# Hub_USB_2_0.net
KiCad netlist of a schematic drawn in EAGLE
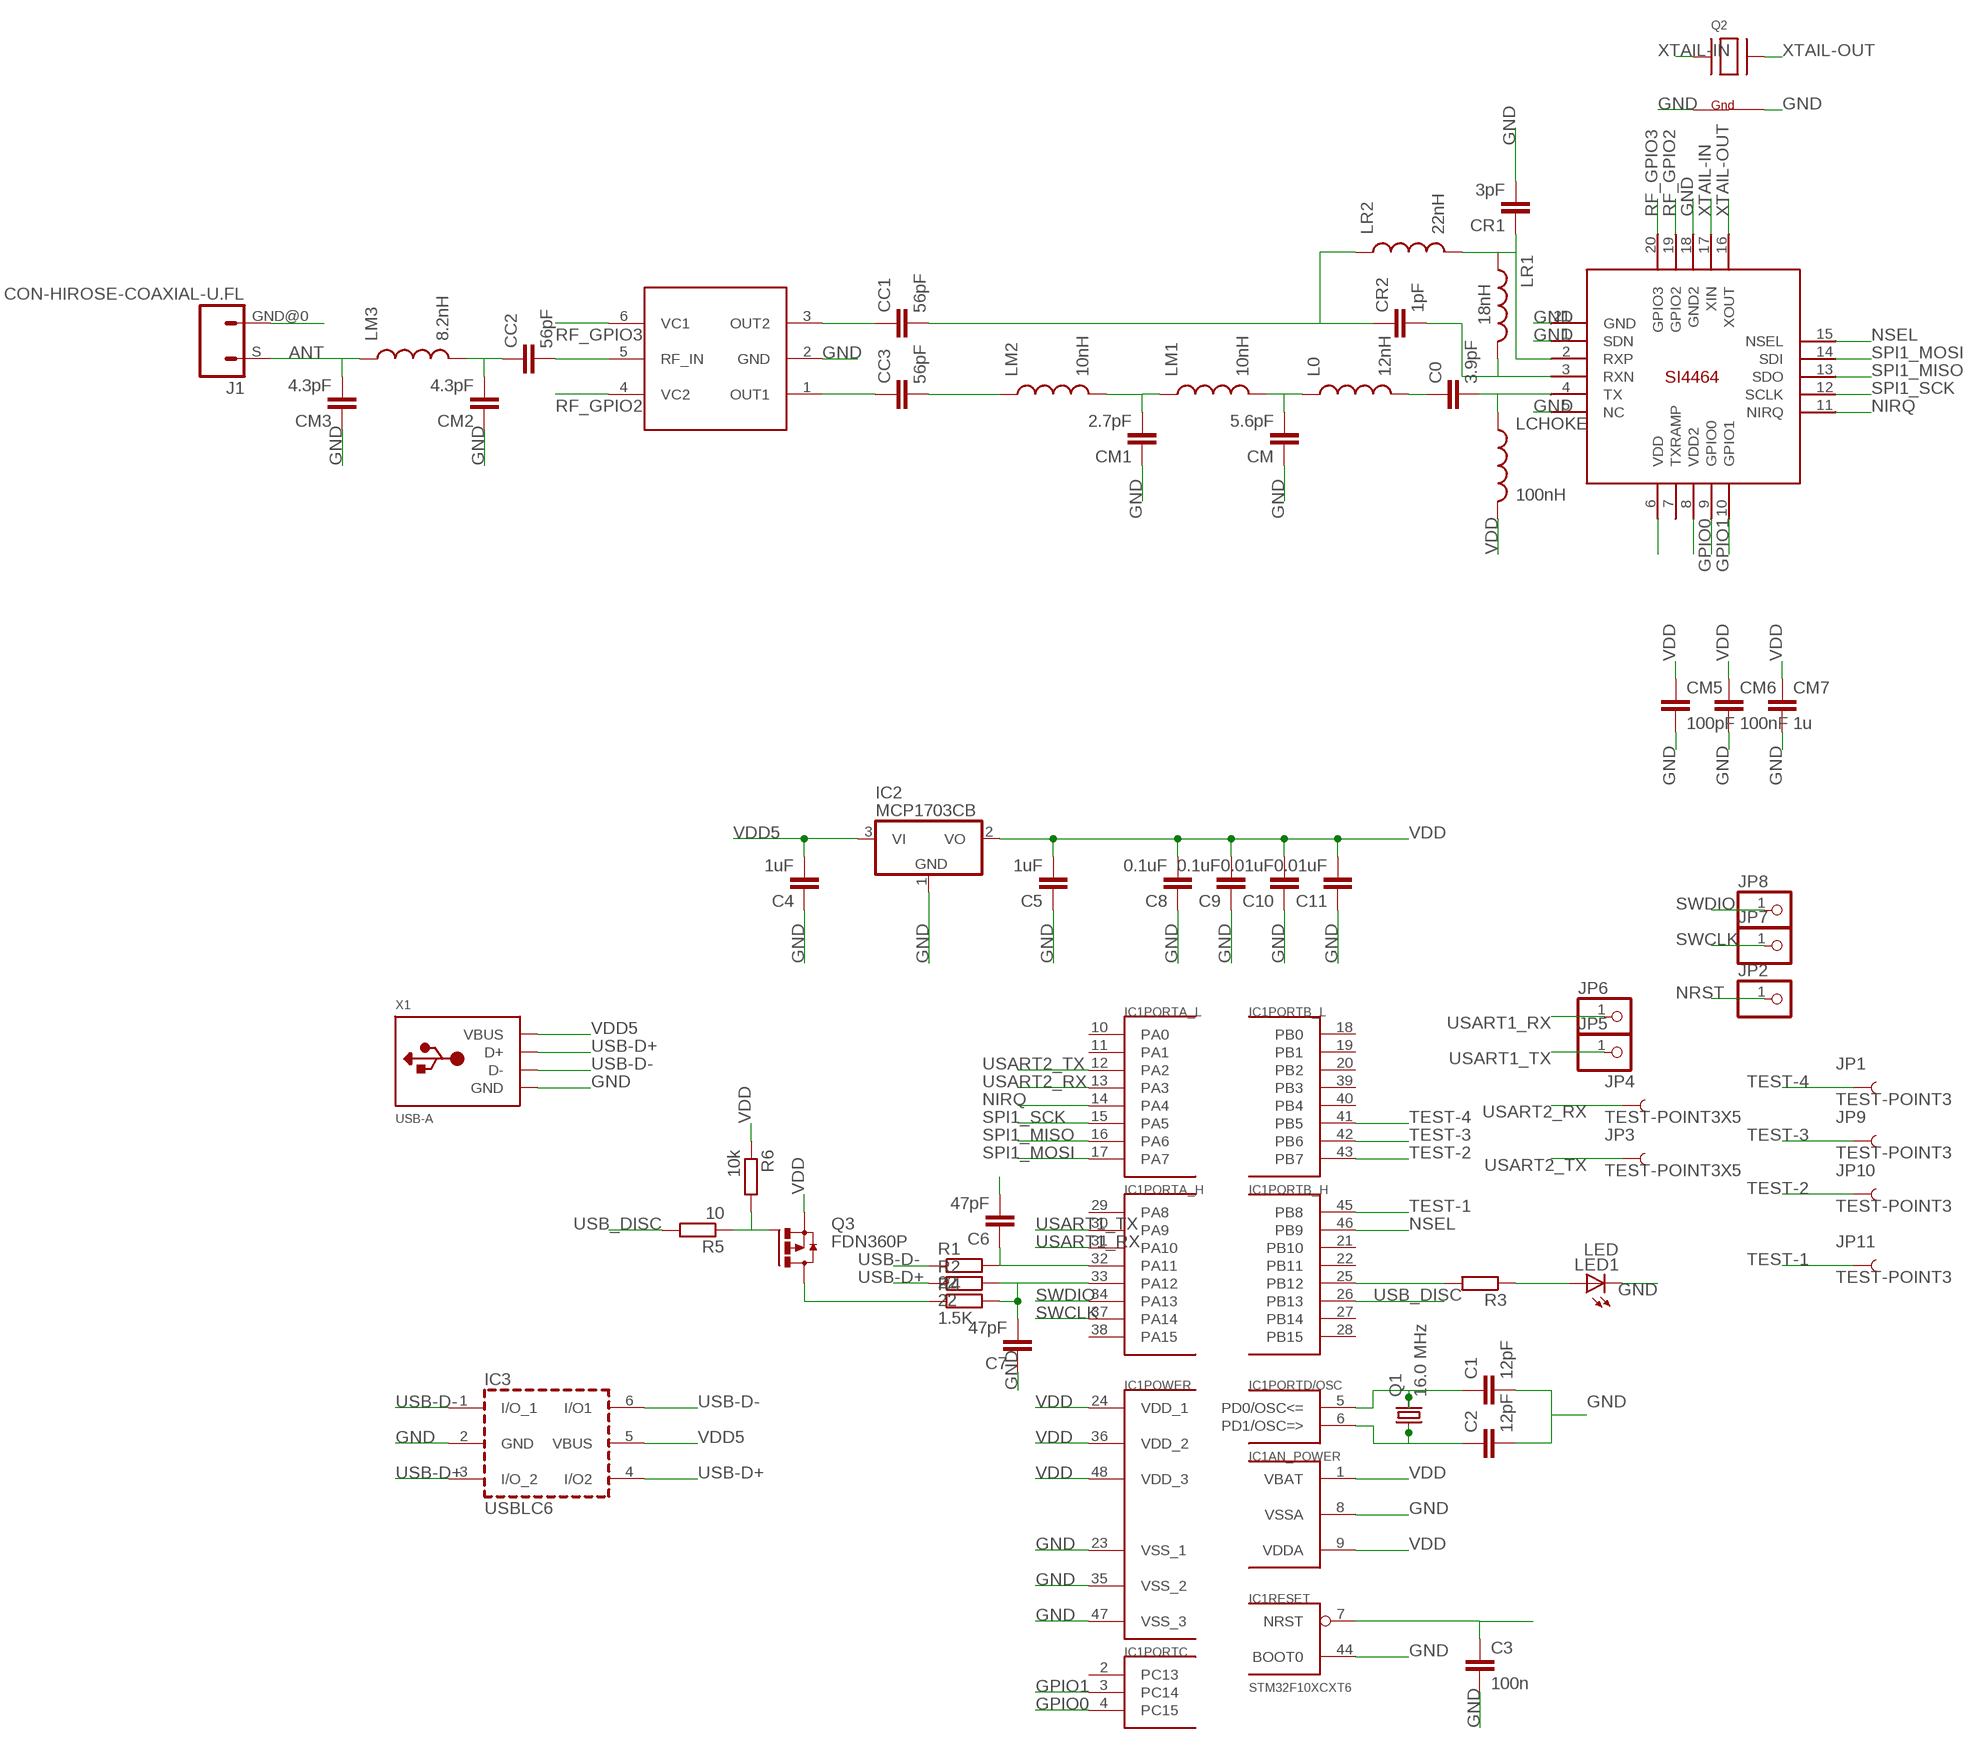
[diagram p0: schematic, sheet 1]

(export (version "E")
  (design (tool "Eeschema 10.0.6"))
  (components
    (comp (ref "C0")
      (value "3.9pF")
      (footprint "eagle-import:C0402")
      (libsource (lib "eagle-import") (part "C-EUC0402"))
    )
    (comp (ref "C1")
      (value "12pF")
      (footprint "eagle-import:C0603K")
      (libsource (lib "eagle-import") (part "C-EUC0603K"))
    )
    (comp (ref "C2")
      (value "12pF")
      (footprint "eagle-import:C0603K")
      (libsource (lib "eagle-import") (part "C-EUC0603K"))
    )
    (comp (ref "C3")
      (value "100n")
      (footprint "eagle-import:C0805")
      (libsource (lib "eagle-import") (part "C-EUC0805"))
    )
    (comp (ref "C4")
      (value "1uF")
      (footprint "eagle-import:C0805")
      (libsource (lib "eagle-import") (part "C-EUC0805"))
    )
    (comp (ref "C5")
      (value "1uF")
      (footprint "eagle-import:C0805")
      (libsource (lib "eagle-import") (part "C-EUC0805"))
    )
    (comp (ref "C6")
      (value "47pF")
      (footprint "eagle-import:C0805")
      (libsource (lib "eagle-import") (part "C-EUC0805"))
    )
    (comp (ref "C7")
      (value "47pF")
      (footprint "eagle-import:C0805")
      (libsource (lib "eagle-import") (part "C-EUC0805"))
    )
    (comp (ref "C8")
      (value "0.1uF")
      (footprint "eagle-import:C0805")
      (libsource (lib "eagle-import") (part "C-EUC0805"))
    )
    (comp (ref "C9")
      (value "0.1uF")
      (footprint "eagle-import:C0805")
      (libsource (lib "eagle-import") (part "C-EUC0805"))
    )
    (comp (ref "C10")
      (value "0.01uF")
      (footprint "eagle-import:C0805")
      (libsource (lib "eagle-import") (part "C-EUC0805"))
    )
    (comp (ref "C11")
      (value "0.01uF")
      (footprint "eagle-import:C0805")
      (libsource (lib "eagle-import") (part "C-EUC0805"))
    )
    (comp (ref "CC1")
      (value "56pF")
      (footprint "eagle-import:C0402")
      (libsource (lib "eagle-import") (part "C-EUC0402"))
    )
    (comp (ref "CC2")
      (value "56pF")
      (footprint "eagle-import:C0402")
      (libsource (lib "eagle-import") (part "C-EUC0402"))
    )
    (comp (ref "CC3")
      (value "56pF")
      (footprint "eagle-import:C0402")
      (libsource (lib "eagle-import") (part "C-EUC0402"))
    )
    (comp (ref "CM")
      (value "5.6pF")
      (footprint "eagle-import:C0402")
      (libsource (lib "eagle-import") (part "C-EUC0402"))
    )
    (comp (ref "CM1")
      (value "2.7pF")
      (footprint "eagle-import:C0402")
      (libsource (lib "eagle-import") (part "C-EUC0402"))
    )
    (comp (ref "CM2")
      (value "4.3pF")
      (footprint "eagle-import:C0402")
      (libsource (lib "eagle-import") (part "C-EUC0402"))
    )
    (comp (ref "CM3")
      (value "4.3pF")
      (footprint "eagle-import:C0402")
      (libsource (lib "eagle-import") (part "C-EUC0402"))
    )
    (comp (ref "CM5")
      (value "100pF")
      (footprint "eagle-import:C0402")
      (libsource (lib "eagle-import") (part "C-EUC0402"))
    )
    (comp (ref "CM6")
      (value "100nF")
      (footprint "eagle-import:C0402")
      (libsource (lib "eagle-import") (part "C-EUC0402"))
    )
    (comp (ref "CM7")
      (value "1u")
      (footprint "eagle-import:C0402")
      (libsource (lib "eagle-import") (part "C-EUC0402"))
    )
    (comp (ref "CR1")
      (value "3pF")
      (footprint "eagle-import:C0402")
      (libsource (lib "eagle-import") (part "C-EUC0402"))
    )
    (comp (ref "CR2")
      (value "1pF")
      (footprint "eagle-import:C0402")
      (libsource (lib "eagle-import") (part "C-EUC0402"))
    )
    (comp (ref "IC1")
      (value "STM32F10XCXT6")
      (footprint "eagle-import:TQFP48")
      (libsource (lib "eagle-import") (part "STM32F10XCXT6"))
    )
    (comp (ref "IC2")
      (value "MCP1703CB")
      (footprint "eagle-import:SOT23")
      (libsource (lib "eagle-import") (part "MCP1703CB"))
    )
    (comp (ref "IC3")
      (value "USBLC6")
      (footprint "eagle-import:SOT-23-6L")
      (libsource (lib "eagle-import") (part "IC_USBLC6-2"))
    )
    (comp (ref "J1")
      (value "CON-HIROSE-COAXIAL-U.FL")
      (footprint "eagle-import:CON-U.FL")
      (libsource (lib "eagle-import") (part "CON-HIROSE-COAXIAL-U.FL"))
    )
    (comp (ref "JP1")
      (value "TEST-POINT3")
      (footprint "eagle-import:PAD.03X.03")
      (libsource (lib "eagle-import") (part "TEST-POINT3"))
    )
    (comp (ref "JP2")
      (value "PINHD-1X1")
      (footprint "eagle-import:1X01")
      (libsource (lib "eagle-import") (part "pinhead_PINHD-1X1"))
    )
    (comp (ref "JP3")
      (value "TEST-POINT3X5")
      (footprint "eagle-import:PAD.03X.05")
      (libsource (lib "eagle-import") (part "TEST-POINT3X5"))
    )
    (comp (ref "JP4")
      (value "TEST-POINT3X5")
      (footprint "eagle-import:PAD.03X.05")
      (libsource (lib "eagle-import") (part "TEST-POINT3X5"))
    )
    (comp (ref "JP5")
      (value "PINHD-1X1CB")
      (footprint "eagle-import:1X01-CLEANBIG")
      (libsource (lib "eagle-import") (part "PINHD-1X1CB"))
    )
    (comp (ref "JP6")
      (value "PINHD-1X1CB")
      (footprint "eagle-import:1X01-CLEANBIG")
      (libsource (lib "eagle-import") (part "PINHD-1X1CB"))
    )
    (comp (ref "JP7")
      (value "PINHD-1X1")
      (footprint "eagle-import:1X01")
      (libsource (lib "eagle-import") (part "pinhead_PINHD-1X1"))
    )
    (comp (ref "JP8")
      (value "PINHD-1X1")
      (footprint "eagle-import:1X01")
      (libsource (lib "eagle-import") (part "pinhead_PINHD-1X1"))
    )
    (comp (ref "JP9")
      (value "TEST-POINT3")
      (footprint "eagle-import:PAD.03X.03")
      (libsource (lib "eagle-import") (part "TEST-POINT3"))
    )
    (comp (ref "JP10")
      (value "TEST-POINT3")
      (footprint "eagle-import:PAD.03X.03")
      (libsource (lib "eagle-import") (part "TEST-POINT3"))
    )
    (comp (ref "JP11")
      (value "TEST-POINT3")
      (footprint "eagle-import:PAD.03X.03")
      (libsource (lib "eagle-import") (part "TEST-POINT3"))
    )
    (comp (ref "L0")
      (value "12nH")
      (footprint "eagle-import:C0402")
      (libsource (lib "eagle-import") (part "INDUCTOR0402"))
    )
    (comp (ref "LCHOKE")
      (value "100nH")
      (footprint "eagle-import:C0402")
      (libsource (lib "eagle-import") (part "INDUCTOR0402"))
    )
    (comp (ref "LED1")
      (value "LED")
      (footprint "eagle-import:CHIPLED_0805")
      (libsource (lib "eagle-import") (part "LEDCHIPLED_0805"))
    )
    (comp (ref "LM1")
      (value "10nH")
      (footprint "eagle-import:C0402")
      (libsource (lib "eagle-import") (part "INDUCTOR0402"))
    )
    (comp (ref "LM2")
      (value "10nH")
      (footprint "eagle-import:C0402")
      (libsource (lib "eagle-import") (part "INDUCTOR0402"))
    )
    (comp (ref "LM3")
      (value "8.2nH")
      (footprint "eagle-import:C0402")
      (libsource (lib "eagle-import") (part "INDUCTOR0402"))
    )
    (comp (ref "LR1")
      (value "18nH")
      (footprint "eagle-import:C0402")
      (libsource (lib "eagle-import") (part "INDUCTOR0402"))
    )
    (comp (ref "LR2")
      (value "22nH")
      (footprint "eagle-import:C0402")
      (libsource (lib "eagle-import") (part "INDUCTOR0402"))
    )
    (comp (ref "Q1")
      (value "16.0 MHz")
      (footprint "eagle-import:CRYSTAL-SMD-3.2X2.5")
      (libsource (lib "eagle-import") (part "CRYSTAL3.2X2.5"))
    )
    (comp (ref "Q2")
      (value "XTAL-4-3225")
      (footprint "eagle-import:NX3225")
      (libsource (lib "eagle-import") (part "XTAL-4-3225"))
    )
    (comp (ref "Q3")
      (value "FDN360P")
      (footprint "eagle-import:SUPER-SOT3")
      (libsource (lib "eagle-import") (part "FDN360P"))
    )
    (comp (ref "R1")
      (value "22")
      (footprint "eagle-import:R0805")
      (libsource (lib "eagle-import") (part "R-EU_R0805"))
    )
    (comp (ref "R2")
      (value "22")
      (footprint "eagle-import:R0805")
      (libsource (lib "eagle-import") (part "R-EU_R0805"))
    )
    (comp (ref "R3")
      (value "R-EU_R0805")
      (footprint "eagle-import:R0805")
      (libsource (lib "eagle-import") (part "R-EU_R0805"))
    )
    (comp (ref "R4")
      (value "1.5K")
      (footprint "eagle-import:R0805")
      (libsource (lib "eagle-import") (part "R-EU_R0805"))
    )
    (comp (ref "R5")
      (value "10")
      (footprint "eagle-import:R0805")
      (libsource (lib "eagle-import") (part "R-EU_R0805"))
    )
    (comp (ref "R6")
      (value "10k")
      (footprint "eagle-import:R0805")
      (libsource (lib "eagle-import") (part "R-EU_R0805"))
    )
    (comp (ref "U$1")
      (value "SI4464")
      (footprint "eagle-import:QFN20+GNDPAD")
      (libsource (lib "eagle-import") (part "SI4464"))
    )
    (comp (ref "U$2")
      (value "UPG2179TB")
      (footprint "eagle-import:SUPER_MINIMOLD")
      (libsource (lib "eagle-import") (part "UPG2179TB"))
    )
    (comp (ref "X1")
      (value "USB-A")
      (footprint "eagle-import:MOLEX_480371000")
      (libsource (lib "eagle-import") (part "USB-A"))
    )
  )
  (nets
    (net (code "1") (name "/ANT") (class "Default")
      (node (ref "CM3") (pin "2") (pinfunction "2_2") (pintype "passive"))
      (node (ref "J1") (pin "S") (pinfunction "1_S") (pintype "passive"))
      (node (ref "LM3") (pin "1") (pinfunction "1_1") (pintype "passive"))
    )
    (net (code "2") (name "/GND") (class "Default")
      (node (ref "C1") (pin "2") (pinfunction "2_2") (pintype "passive"))
      (node (ref "C10") (pin "1") (pinfunction "1_1") (pintype "passive"))
      (node (ref "C11") (pin "1") (pinfunction "1_1") (pintype "passive"))
      (node (ref "C2") (pin "2") (pinfunction "2_2") (pintype "passive"))
      (node (ref "C3") (pin "2") (pinfunction "2_2") (pintype "passive"))
      (node (ref "C4") (pin "1") (pinfunction "1_1") (pintype "passive"))
      (node (ref "C5") (pin "1") (pinfunction "1_1") (pintype "passive"))
      (node (ref "C6") (pin "2") (pinfunction "2_2") (pintype "passive"))
      (node (ref "C7") (pin "1") (pinfunction "1_1") (pintype "passive"))
      (node (ref "C8") (pin "1") (pinfunction "1_1") (pintype "passive"))
      (node (ref "C9") (pin "1") (pinfunction "1_1") (pintype "passive"))
      (node (ref "CM") (pin "1") (pinfunction "1_1") (pintype "passive"))
      (node (ref "CM1") (pin "1") (pinfunction "1_1") (pintype "passive"))
      (node (ref "CM2") (pin "1") (pinfunction "1_1") (pintype "passive"))
      (node (ref "CM3") (pin "1") (pinfunction "1_1") (pintype "passive"))
      (node (ref "CM5") (pin "2") (pinfunction "2_2") (pintype "passive"))
      (node (ref "CM6") (pin "2") (pinfunction "2_2") (pintype "passive"))
      (node (ref "CM7") (pin "2") (pinfunction "2_2") (pintype "passive"))
      (node (ref "CR1") (pin "2") (pinfunction "2_2") (pintype "passive"))
      (node (ref "IC1") (pin "23") (pinfunction "VSS_1_23") (pintype "power_in"))
      (node (ref "IC1") (pin "35") (pinfunction "VSS_2_35") (pintype "power_in"))
      (node (ref "IC1") (pin "44") (pinfunction "BOOT0_44") (pintype "input"))
      (node (ref "IC1") (pin "47") (pinfunction "VSS_3_47") (pintype "power_in"))
      (node (ref "IC1") (pin "8") (pinfunction "VSSA_8") (pintype "power_in"))
      (node (ref "IC2") (pin "1") (pinfunction "GND_1") (pintype "passive"))
      (node (ref "IC3") (pin "2") (pinfunction "GND_2") (pintype "bidirectional"))
      (node (ref "J1") (pin "GND@0") (pinfunction "2_GND@0") (pintype "passive"))
      (node (ref "LED1") (pin "C") (pinfunction "C_C") (pintype "passive"))
      (node (ref "Q2") (pin "2") (pinfunction "G2_2") (pintype "power_in"))
      (node (ref "Q2") (pin "4") (pinfunction "G1_4") (pintype "power_in"))
      (node (ref "U$1") (pin "1") (pinfunction "SDN_1") (pintype "bidirectional"))
      (node (ref "U$1") (pin "18") (pinfunction "GND2_18") (pintype "bidirectional"))
      (node (ref "U$1") (pin "21") (pinfunction "GND_21") (pintype "bidirectional"))
      (node (ref "U$1") (pin "5") (pinfunction "NC _5") (pintype "bidirectional"))
      (node (ref "U$2") (pin "2") (pinfunction "GND_2") (pintype "bidirectional"))
      (node (ref "X1") (pin "4") (pinfunction "GND_4") (pintype "power_in"))
    )
    (net (code "3") (name "/GPIO0") (class "Default")
      (node (ref "IC1") (pin "4") (pinfunction "PC15_4") (pintype "bidirectional"))
      (node (ref "U$1") (pin "9") (pinfunction "GPIO0_9") (pintype "bidirectional"))
    )
    (net (code "4") (name "/GPIO1") (class "Default")
      (node (ref "IC1") (pin "3") (pinfunction "PC14_3") (pintype "bidirectional"))
      (node (ref "U$1") (pin "10") (pinfunction "GPIO1_10") (pintype "bidirectional"))
    )
    (net (code "5") (name "/NIRQ") (class "Default")
      (node (ref "IC1") (pin "14") (pinfunction "PA4_14") (pintype "bidirectional"))
      (node (ref "U$1") (pin "11") (pinfunction "NIRQ_11") (pintype "bidirectional"))
    )
    (net (code "6") (name "/NRST") (class "Default")
      (node (ref "C3") (pin "1") (pinfunction "1_1") (pintype "passive"))
      (node (ref "IC1") (pin "7") (pinfunction "NRST_7") (pintype "input"))
      (node (ref "JP2") (pin "1") (pinfunction "1_1") (pintype "passive"))
    )
    (net (code "7") (name "/NSEL") (class "Default")
      (node (ref "IC1") (pin "46") (pinfunction "PB9_46") (pintype "bidirectional"))
      (node (ref "U$1") (pin "15") (pinfunction "NSEL_15") (pintype "bidirectional"))
    )
    (net (code "8") (name "/RF_GPIO2") (class "Default")
      (node (ref "U$1") (pin "19") (pinfunction "GPIO2_19") (pintype "bidirectional"))
      (node (ref "U$2") (pin "4") (pinfunction "VC2_4") (pintype "bidirectional"))
    )
    (net (code "9") (name "/RF_GPIO3") (class "Default")
      (node (ref "U$1") (pin "20") (pinfunction "GPIO3_20") (pintype "bidirectional"))
      (node (ref "U$2") (pin "6") (pinfunction "VC1_6") (pintype "bidirectional"))
    )
    (net (code "10") (name "/SPI1_MISO") (class "Default")
      (node (ref "IC1") (pin "16") (pinfunction "PA6_16") (pintype "bidirectional"))
      (node (ref "U$1") (pin "13") (pinfunction "SDO_13") (pintype "bidirectional"))
    )
    (net (code "11") (name "/SPI1_MOSI") (class "Default")
      (node (ref "IC1") (pin "17") (pinfunction "PA7_17") (pintype "bidirectional"))
      (node (ref "U$1") (pin "14") (pinfunction "SDI_14") (pintype "bidirectional"))
    )
    (net (code "12") (name "/SPI1_SCK") (class "Default")
      (node (ref "IC1") (pin "15") (pinfunction "PA5_15") (pintype "bidirectional"))
      (node (ref "U$1") (pin "12") (pinfunction "SCLK_12") (pintype "bidirectional"))
    )
    (net (code "13") (name "/SWCLK") (class "Default")
      (node (ref "IC1") (pin "37") (pinfunction "PA14_37") (pintype "bidirectional"))
      (node (ref "JP7") (pin "1") (pinfunction "1_1") (pintype "passive"))
    )
    (net (code "14") (name "/SWDIO") (class "Default")
      (node (ref "IC1") (pin "34") (pinfunction "PA13_34") (pintype "bidirectional"))
      (node (ref "JP8") (pin "1") (pinfunction "1_1") (pintype "passive"))
    )
    (net (code "15") (name "/TEST-1") (class "Default")
      (node (ref "IC1") (pin "45") (pinfunction "PB8_45") (pintype "bidirectional"))
      (node (ref "JP11") (pin "P$1") (pinfunction "1_P$1") (pintype "bidirectional"))
    )
    (net (code "16") (name "/TEST-2") (class "Default")
      (node (ref "IC1") (pin "43") (pinfunction "PB7_43") (pintype "bidirectional"))
      (node (ref "JP10") (pin "P$1") (pinfunction "1_P$1") (pintype "bidirectional"))
    )
    (net (code "17") (name "/TEST-3") (class "Default")
      (node (ref "IC1") (pin "42") (pinfunction "PB6_42") (pintype "bidirectional"))
      (node (ref "JP9") (pin "P$1") (pinfunction "1_P$1") (pintype "bidirectional"))
    )
    (net (code "18") (name "/TEST-4") (class "Default")
      (node (ref "IC1") (pin "41") (pinfunction "PB5_41") (pintype "bidirectional"))
      (node (ref "JP1") (pin "P$1") (pinfunction "1_P$1") (pintype "bidirectional"))
    )
    (net (code "19") (name "/USART1_RX") (class "Default")
      (node (ref "IC1") (pin "31") (pinfunction "PA10_31") (pintype "bidirectional"))
      (node (ref "JP6") (pin "1") (pinfunction "1_1") (pintype "passive"))
    )
    (net (code "20") (name "/USART1_TX") (class "Default")
      (node (ref "IC1") (pin "30") (pinfunction "PA9_30") (pintype "bidirectional"))
      (node (ref "JP5") (pin "1") (pinfunction "1_1") (pintype "passive"))
    )
    (net (code "21") (name "/USART2_RX") (class "Default")
      (node (ref "IC1") (pin "13") (pinfunction "PA3_13") (pintype "bidirectional"))
      (node (ref "JP4") (pin "P$1") (pinfunction "1_P$1") (pintype "bidirectional"))
    )
    (net (code "22") (name "/USART2_TX") (class "Default")
      (node (ref "IC1") (pin "12") (pinfunction "PA2_12") (pintype "bidirectional"))
      (node (ref "JP3") (pin "P$1") (pinfunction "1_P$1") (pintype "bidirectional"))
    )
    (net (code "23") (name "/USB-D+") (class "Default")
      (node (ref "IC3") (pin "3") (pinfunction "I/O_2_3") (pintype "bidirectional"))
      (node (ref "IC3") (pin "4") (pinfunction "I/O2_4") (pintype "bidirectional"))
      (node (ref "R2") (pin "1") (pinfunction "1_1") (pintype "passive"))
      (node (ref "X1") (pin "3") (pinfunction "D+_3") (pintype "bidirectional"))
    )
    (net (code "24") (name "/USB-D-") (class "Default")
      (node (ref "IC3") (pin "1") (pinfunction "I/O_1_1") (pintype "bidirectional"))
      (node (ref "IC3") (pin "6") (pinfunction "I/O1_6") (pintype "bidirectional"))
      (node (ref "R1") (pin "1") (pinfunction "1_1") (pintype "passive"))
      (node (ref "X1") (pin "2") (pinfunction "D-_2") (pintype "bidirectional"))
    )
    (net (code "25") (name "/USB_DISC") (class "Default")
      (node (ref "IC1") (pin "26") (pinfunction "PB13_26") (pintype "bidirectional"))
      (node (ref "R5") (pin "2") (pinfunction "2_2") (pintype "passive"))
    )
    (net (code "26") (name "/VDD") (class "Default")
      (node (ref "C10") (pin "2") (pinfunction "2_2") (pintype "passive"))
      (node (ref "C11") (pin "2") (pinfunction "2_2") (pintype "passive"))
      (node (ref "C5") (pin "2") (pinfunction "2_2") (pintype "passive"))
      (node (ref "C8") (pin "2") (pinfunction "2_2") (pintype "passive"))
      (node (ref "C9") (pin "2") (pinfunction "2_2") (pintype "passive"))
      (node (ref "CM5") (pin "1") (pinfunction "1_1") (pintype "passive"))
      (node (ref "CM6") (pin "1") (pinfunction "1_1") (pintype "passive"))
      (node (ref "CM7") (pin "1") (pinfunction "1_1") (pintype "passive"))
      (node (ref "IC1") (pin "1") (pinfunction "VBAT_1") (pintype "power_in"))
      (node (ref "IC1") (pin "24") (pinfunction "VDD_1_24") (pintype "power_in"))
      (node (ref "IC1") (pin "36") (pinfunction "VDD_2_36") (pintype "power_in"))
      (node (ref "IC1") (pin "48") (pinfunction "VDD_3_48") (pintype "power_in"))
      (node (ref "IC1") (pin "9") (pinfunction "VDDA_9") (pintype "power_in"))
      (node (ref "IC2") (pin "2") (pinfunction "VO_2") (pintype "passive"))
      (node (ref "LCHOKE") (pin "2") (pinfunction "2_2") (pintype "passive"))
      (node (ref "Q3") (pin "2") (pinfunction "S_2") (pintype "passive"))
      (node (ref "R6") (pin "1") (pinfunction "1_1") (pintype "passive"))
      (node (ref "U$1") (pin "6") (pinfunction "VDD_6") (pintype "bidirectional"))
      (node (ref "U$1") (pin "8") (pinfunction "VDD2_8") (pintype "bidirectional"))
    )
    (net (code "27") (name "/VDD5") (class "Default")
      (node (ref "C4") (pin "2") (pinfunction "2_2") (pintype "passive"))
      (node (ref "IC2") (pin "3") (pinfunction "VI_3") (pintype "input"))
      (node (ref "IC3") (pin "5") (pinfunction "VBUS_5") (pintype "bidirectional"))
      (node (ref "X1") (pin "1") (pinfunction "VBUS_1") (pintype "power_in"))
    )
    (net (code "28") (name "/XTAIL-IN") (class "Default")
      (node (ref "Q2") (pin "1") (pinfunction "X1_1") (pintype "bidirectional"))
      (node (ref "U$1") (pin "17") (pinfunction "XIN_17") (pintype "bidirectional"))
    )
    (net (code "29") (name "/XTAIL-OUT") (class "Default")
      (node (ref "Q2") (pin "3") (pinfunction "X2_3") (pintype "bidirectional"))
      (node (ref "U$1") (pin "16") (pinfunction "XOUT_16") (pintype "bidirectional"))
    )
    (net (code "30") (name "Net-(C0-Pad1)") (class "Default")
      (node (ref "C0") (pin "1") (pinfunction "1_1") (pintype "passive"))
      (node (ref "L0") (pin "2") (pinfunction "2_2") (pintype "passive"))
    )
    (net (code "31") (name "Net-(CC1-Pad2)") (class "Default")
      (node (ref "CC1") (pin "2") (pinfunction "2_2") (pintype "passive"))
      (node (ref "CR2") (pin "1") (pinfunction "1_1") (pintype "passive"))
      (node (ref "LR2") (pin "1") (pinfunction "1_1") (pintype "passive"))
    )
    (net (code "32") (name "Net-(CC2-Pad1)") (class "Default")
      (node (ref "CC2") (pin "1") (pinfunction "1_1") (pintype "passive"))
      (node (ref "CM2") (pin "2") (pinfunction "2_2") (pintype "passive"))
      (node (ref "LM3") (pin "2") (pinfunction "2_2") (pintype "passive"))
    )
    (net (code "33") (name "Net-(CC3-Pad2)") (class "Default")
      (node (ref "CC3") (pin "2") (pinfunction "2_2") (pintype "passive"))
      (node (ref "LM2") (pin "1") (pinfunction "1_1") (pintype "passive"))
    )
    (net (code "34") (name "Net-(CM-Pad2)") (class "Default")
      (node (ref "CM") (pin "2") (pinfunction "2_2") (pintype "passive"))
      (node (ref "L0") (pin "1") (pinfunction "1_1") (pintype "passive"))
      (node (ref "LM1") (pin "2") (pinfunction "2_2") (pintype "passive"))
    )
    (net (code "35") (name "Net-(CM1-Pad2)") (class "Default")
      (node (ref "CM1") (pin "2") (pinfunction "2_2") (pintype "passive"))
      (node (ref "LM1") (pin "1") (pinfunction "1_1") (pintype "passive"))
      (node (ref "LM2") (pin "2") (pinfunction "2_2") (pintype "passive"))
    )
    (net (code "36") (name "Net-(IC1B-PA11)") (class "Default")
      (node (ref "C6") (pin "1") (pinfunction "1_1") (pintype "passive"))
      (node (ref "IC1") (pin "32") (pinfunction "PA11_32") (pintype "bidirectional"))
      (node (ref "R1") (pin "2") (pinfunction "2_2") (pintype "passive"))
    )
    (net (code "37") (name "Net-(IC1B-PA12)") (class "Default")
      (node (ref "C7") (pin "2") (pinfunction "2_2") (pintype "passive"))
      (node (ref "IC1") (pin "33") (pinfunction "PA12_33") (pintype "bidirectional"))
      (node (ref "R2") (pin "2") (pinfunction "2_2") (pintype "passive"))
      (node (ref "R4") (pin "2") (pinfunction "2_2") (pintype "passive"))
    )
    (net (code "38") (name "Net-(IC1D-PB12)") (class "Default")
      (node (ref "IC1") (pin "25") (pinfunction "PB12_25") (pintype "bidirectional"))
      (node (ref "R3") (pin "2") (pinfunction "2_2") (pintype "passive"))
    )
    (net (code "39") (name "Net-(IC1G-PD0{slash}OSC<=)") (class "Default")
      (node (ref "C1") (pin "1") (pinfunction "1_1") (pintype "passive"))
      (node (ref "IC1") (pin "5") (pinfunction "PD0/OSC<=_5") (pintype "bidirectional"))
      (node (ref "Q1") (pin "3") (pinfunction "2_3") (pintype "passive"))
    )
    (net (code "40") (name "Net-(IC1G-PD1{slash}OSC=>)") (class "Default")
      (node (ref "C2") (pin "1") (pinfunction "1_1") (pintype "passive"))
      (node (ref "IC1") (pin "6") (pinfunction "PD1/OSC=>_6") (pintype "bidirectional"))
      (node (ref "Q1") (pin "1") (pinfunction "1_1") (pintype "passive"))
    )
    (net (code "41") (name "Net-(LED1-PadA)") (class "Default")
      (node (ref "LED1") (pin "A") (pinfunction "A_A") (pintype "passive"))
      (node (ref "R3") (pin "1") (pinfunction "1_1") (pintype "passive"))
    )
    (net (code "42") (name "Net-(Q3-D)") (class "Default")
      (node (ref "Q3") (pin "3") (pinfunction "D_3") (pintype "passive"))
      (node (ref "R4") (pin "1") (pinfunction "1_1") (pintype "passive"))
    )
    (net (code "43") (name "Net-(Q3-G)") (class "Default")
      (node (ref "Q3") (pin "1") (pinfunction "G_1") (pintype "passive"))
      (node (ref "R5") (pin "1") (pinfunction "1_1") (pintype "passive"))
      (node (ref "R6") (pin "2") (pinfunction "2_2") (pintype "passive"))
    )
    (net (code "44") (name "Net-(U$1-RXN)") (class "Default")
      (node (ref "CR2") (pin "2") (pinfunction "2_2") (pintype "passive"))
      (node (ref "LR1") (pin "2") (pinfunction "2_2") (pintype "passive"))
      (node (ref "U$1") (pin "3") (pinfunction "RXN_3") (pintype "bidirectional"))
    )
    (net (code "45") (name "Net-(U$1-RXP)") (class "Default")
      (node (ref "CR1") (pin "1") (pinfunction "1_1") (pintype "passive"))
      (node (ref "LR1") (pin "1") (pinfunction "1_1") (pintype "passive"))
      (node (ref "LR2") (pin "2") (pinfunction "2_2") (pintype "passive"))
      (node (ref "U$1") (pin "2") (pinfunction "RXP_2") (pintype "bidirectional"))
    )
    (net (code "46") (name "Net-(U$1-TX)") (class "Default")
      (node (ref "C0") (pin "2") (pinfunction "2_2") (pintype "passive"))
      (node (ref "LCHOKE") (pin "1") (pinfunction "1_1") (pintype "passive"))
      (node (ref "U$1") (pin "4") (pinfunction "TX_4") (pintype "bidirectional"))
    )
    (net (code "47") (name "Net-(U$2-OUT1)") (class "Default")
      (node (ref "CC3") (pin "1") (pinfunction "1_1") (pintype "passive"))
      (node (ref "U$2") (pin "1") (pinfunction "OUT1_1") (pintype "bidirectional"))
    )
    (net (code "48") (name "Net-(U$2-OUT2)") (class "Default")
      (node (ref "CC1") (pin "1") (pinfunction "1_1") (pintype "passive"))
      (node (ref "U$2") (pin "3") (pinfunction "OUT2_3") (pintype "bidirectional"))
    )
    (net (code "49") (name "Net-(U$2-RF_IN)") (class "Default")
      (node (ref "CC2") (pin "2") (pinfunction "2_2") (pintype "passive"))
      (node (ref "U$2") (pin "5") (pinfunction "RF_IN_5") (pintype "bidirectional"))
    )
    (net (code "50") (name "unconnected-(IC1B-PA8-Pad29)") (class "Default")
      (node (ref "IC1") (pin "29") (pinfunction "PA8_29") (pintype "bidirectional"))
    )
    (net (code "51") (name "unconnected-(IC1B-PA15-Pad38)") (class "Default")
      (node (ref "IC1") (pin "38") (pinfunction "PA15_38") (pintype "bidirectional"))
    )
    (net (code "52") (name "unconnected-(IC1C-PA0-Pad10)") (class "Default")
      (node (ref "IC1") (pin "10") (pinfunction "PA0_10") (pintype "bidirectional"))
    )
    (net (code "53") (name "unconnected-(IC1C-PA1-Pad11)") (class "Default")
      (node (ref "IC1") (pin "11") (pinfunction "PA1_11") (pintype "bidirectional"))
    )
    (net (code "54") (name "unconnected-(IC1D-PB10-Pad21)") (class "Default")
      (node (ref "IC1") (pin "21") (pinfunction "PB10_21") (pintype "bidirectional"))
    )
    (net (code "55") (name "unconnected-(IC1D-PB11-Pad22)") (class "Default")
      (node (ref "IC1") (pin "22") (pinfunction "PB11_22") (pintype "bidirectional"))
    )
    (net (code "56") (name "unconnected-(IC1D-PB14-Pad27)") (class "Default")
      (node (ref "IC1") (pin "27") (pinfunction "PB14_27") (pintype "bidirectional"))
    )
    (net (code "57") (name "unconnected-(IC1D-PB15-Pad28)") (class "Default")
      (node (ref "IC1") (pin "28") (pinfunction "PB15_28") (pintype "bidirectional"))
    )
    (net (code "58") (name "unconnected-(IC1E-PB0-Pad18)") (class "Default")
      (node (ref "IC1") (pin "18") (pinfunction "PB0_18") (pintype "bidirectional"))
    )
    (net (code "59") (name "unconnected-(IC1E-PB1-Pad19)") (class "Default")
      (node (ref "IC1") (pin "19") (pinfunction "PB1_19") (pintype "bidirectional"))
    )
    (net (code "60") (name "unconnected-(IC1E-PB2-Pad20)") (class "Default")
      (node (ref "IC1") (pin "20") (pinfunction "PB2_20") (pintype "bidirectional"))
    )
    (net (code "61") (name "unconnected-(IC1E-PB3-Pad39)") (class "Default")
      (node (ref "IC1") (pin "39") (pinfunction "PB3_39") (pintype "bidirectional"))
    )
    (net (code "62") (name "unconnected-(IC1E-PB4-Pad40)") (class "Default")
      (node (ref "IC1") (pin "40") (pinfunction "PB4_40") (pintype "bidirectional"))
    )
    (net (code "63") (name "unconnected-(IC1F-PC13-Pad2)") (class "Default")
      (node (ref "IC1") (pin "2") (pinfunction "PC13_2") (pintype "bidirectional"))
    )
    (net (code "64") (name "unconnected-(U$1-TXRAMP-Pad7)") (class "Default")
      (node (ref "U$1") (pin "7") (pinfunction "TXRAMP_7") (pintype "bidirectional"))
    )
  )
)
